# E17-15-CHARGE_SW.net
KiCad netlist of a schematic drawn in Altium Designer
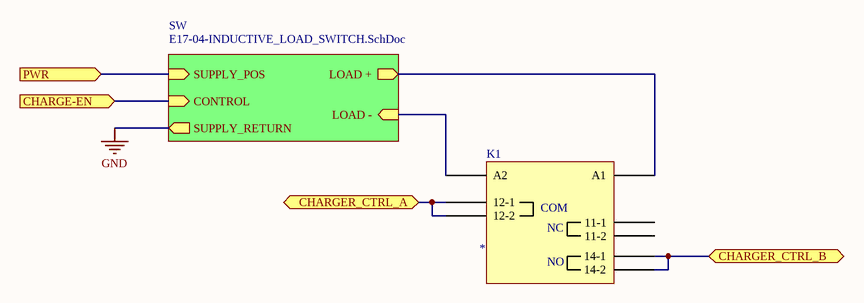
[diagram p0: E17-15-CHARGE_SW.SchDoc]

(export (version "E")
  (design (tool "Eeschema 10.0.6"))
  (components
    (comp (ref "K1")
      (value "*")
      (footprint "TE-7-1393243-5")
      (description "RELAY GEN PURPOSE SPDT 16A 110V")
      (libsource (lib "E17-12_CC") (part "TE-1393240-3"))
    )
  )
  (nets
    (net (code "2") (name "/CHARGER_CTRL_A") (class "Default")
      (node (ref "K1") (pin "2") (pinfunction "12-1_2") (pintype "passive"))
      (node (ref "K1") (pin "7") (pinfunction "12-2_7") (pintype "passive"))
    )
    (net (code "3") (name "/CHARGER_CTRL_B") (class "Default")
      (node (ref "K1") (pin "4") (pinfunction "14-1_4") (pintype "passive"))
      (node (ref "K1") (pin "5") (pinfunction "14-2_5") (pintype "passive"))
    )
    (net (code "4") (name "/LOAD +") (class "Default")
      (node (ref "K1") (pin "8") (pinfunction "A1_8") (pintype "passive"))
    )
    (net (code "5") (name "/LOAD -") (class "Default")
      (node (ref "K1") (pin "1") (pinfunction "A2_1") (pintype "passive"))
    )
    (net (code "8") (name "unconnected-(K1-11-1-Pad3)") (class "Default")
      (node (ref "K1") (pin "3") (pinfunction "11-1_3") (pintype "passive"))
    )
    (net (code "9") (name "unconnected-(K1-11-2-Pad6)") (class "Default")
      (node (ref "K1") (pin "6") (pinfunction "11-2_6") (pintype "passive"))
    )
  )
)
